# 08-NANDStatusLed.net
KiCad netlist of a schematic drawn in Altium Designer
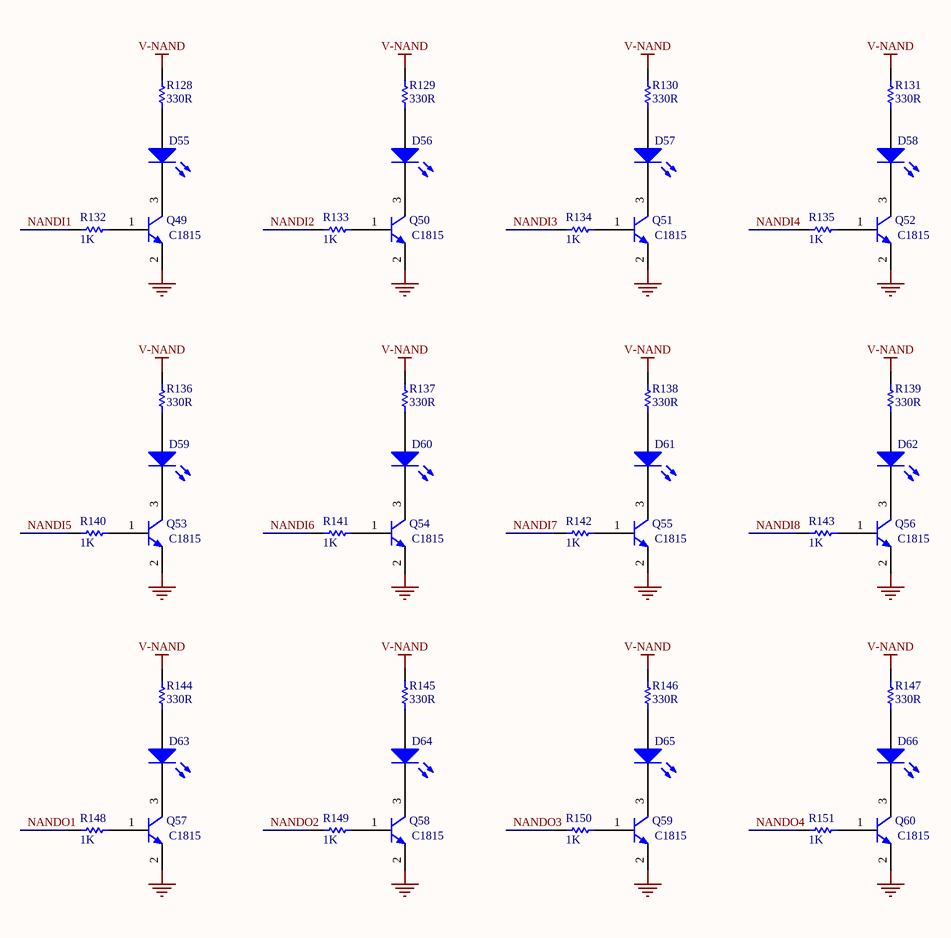
[diagram p0: 08-NANDStatusLed.SchDoc]

(export (version "E")
  (design (tool "Eeschema 10.0.6"))
  (components
    (comp (ref "D55")
      (value "LED")
      (footprint "LED-3528")
      (description "Typical RED, GREEN, YELLOW, AMBER GaAs LED")
      (fields (field (name "PUBLISHER") "Altium Limited"))
      (libsource (lib "Miscellaneous Devices") (part "LED2"))
    )
    (comp (ref "D56")
      (value "LED")
      (footprint "LED-3528")
      (description "Typical RED, GREEN, YELLOW, AMBER GaAs LED")
      (fields (field (name "PUBLISHER") "Altium Limited"))
      (libsource (lib "Miscellaneous Devices") (part "LED2"))
    )
    (comp (ref "D57")
      (value "LED")
      (footprint "LED-3528")
      (description "Typical RED, GREEN, YELLOW, AMBER GaAs LED")
      (fields (field (name "PUBLISHER") "Altium Limited"))
      (libsource (lib "Miscellaneous Devices") (part "LED2"))
    )
    (comp (ref "D58")
      (value "LED")
      (footprint "LED-3528")
      (description "Typical RED, GREEN, YELLOW, AMBER GaAs LED")
      (fields (field (name "PUBLISHER") "Altium Limited"))
      (libsource (lib "Miscellaneous Devices") (part "LED2"))
    )
    (comp (ref "D59")
      (value "LED")
      (footprint "LED-3528")
      (description "Typical RED, GREEN, YELLOW, AMBER GaAs LED")
      (fields (field (name "PUBLISHER") "Altium Limited"))
      (libsource (lib "Miscellaneous Devices") (part "LED2"))
    )
    (comp (ref "D60")
      (value "LED")
      (footprint "LED-3528")
      (description "Typical RED, GREEN, YELLOW, AMBER GaAs LED")
      (fields (field (name "PUBLISHER") "Altium Limited"))
      (libsource (lib "Miscellaneous Devices") (part "LED2"))
    )
    (comp (ref "D61")
      (value "LED")
      (footprint "LED-3528")
      (description "Typical RED, GREEN, YELLOW, AMBER GaAs LED")
      (fields (field (name "PUBLISHER") "Altium Limited"))
      (libsource (lib "Miscellaneous Devices") (part "LED2"))
    )
    (comp (ref "D62")
      (value "LED")
      (footprint "LED-3528")
      (description "Typical RED, GREEN, YELLOW, AMBER GaAs LED")
      (fields (field (name "PUBLISHER") "Altium Limited"))
      (libsource (lib "Miscellaneous Devices") (part "LED2"))
    )
    (comp (ref "D63")
      (value "LED")
      (footprint "LED-3528")
      (description "Typical RED, GREEN, YELLOW, AMBER GaAs LED")
      (fields (field (name "PUBLISHER") "Altium Limited"))
      (libsource (lib "Miscellaneous Devices") (part "LED2"))
    )
    (comp (ref "D64")
      (value "LED")
      (footprint "LED-3528")
      (description "Typical RED, GREEN, YELLOW, AMBER GaAs LED")
      (fields (field (name "PUBLISHER") "Altium Limited"))
      (libsource (lib "Miscellaneous Devices") (part "LED2"))
    )
    (comp (ref "D65")
      (value "LED")
      (footprint "LED-3528")
      (description "Typical RED, GREEN, YELLOW, AMBER GaAs LED")
      (fields (field (name "PUBLISHER") "Altium Limited"))
      (libsource (lib "Miscellaneous Devices") (part "LED2"))
    )
    (comp (ref "D66")
      (value "LED")
      (footprint "LED-3528")
      (description "Typical RED, GREEN, YELLOW, AMBER GaAs LED")
      (fields (field (name "PUBLISHER") "Altium Limited"))
      (libsource (lib "Miscellaneous Devices") (part "LED2"))
    )
    (comp (ref "Q49")
      (value "C1815")
      (footprint "SOT23-321")
      (description "NPN Bipolar Transistor")
      (fields (field (name "Comment") "C1815-SMD"))
      (libsource (lib "Miscellaneous Devices") (part "NPN"))
    )
    (comp (ref "Q50")
      (value "C1815")
      (footprint "SOT23-321")
      (description "NPN Bipolar Transistor")
      (fields (field (name "Comment") "C1815-SMD"))
      (libsource (lib "Miscellaneous Devices") (part "NPN"))
    )
    (comp (ref "Q51")
      (value "C1815")
      (footprint "SOT23-321")
      (description "NPN Bipolar Transistor")
      (fields (field (name "Comment") "C1815-SMD"))
      (libsource (lib "Miscellaneous Devices") (part "NPN"))
    )
    (comp (ref "Q52")
      (value "C1815")
      (footprint "SOT23-321")
      (description "NPN Bipolar Transistor")
      (fields (field (name "Comment") "C1815-SMD"))
      (libsource (lib "Miscellaneous Devices") (part "NPN"))
    )
    (comp (ref "Q53")
      (value "C1815")
      (footprint "SOT23-321")
      (description "NPN Bipolar Transistor")
      (fields (field (name "Comment") "C1815-SMD"))
      (libsource (lib "Miscellaneous Devices") (part "NPN"))
    )
    (comp (ref "Q54")
      (value "C1815")
      (footprint "SOT23-321")
      (description "NPN Bipolar Transistor")
      (fields (field (name "Comment") "C1815-SMD"))
      (libsource (lib "Miscellaneous Devices") (part "NPN"))
    )
    (comp (ref "Q55")
      (value "C1815")
      (footprint "SOT23-321")
      (description "NPN Bipolar Transistor")
      (fields (field (name "Comment") "C1815-SMD"))
      (libsource (lib "Miscellaneous Devices") (part "NPN"))
    )
    (comp (ref "Q56")
      (value "C1815")
      (footprint "SOT23-321")
      (description "NPN Bipolar Transistor")
      (fields (field (name "Comment") "C1815-SMD"))
      (libsource (lib "Miscellaneous Devices") (part "NPN"))
    )
    (comp (ref "Q57")
      (value "C1815")
      (footprint "SOT23-321")
      (description "NPN Bipolar Transistor")
      (fields (field (name "Comment") "C1815-SMD"))
      (libsource (lib "Miscellaneous Devices") (part "NPN"))
    )
    (comp (ref "Q58")
      (value "C1815")
      (footprint "SOT23-321")
      (description "NPN Bipolar Transistor")
      (fields (field (name "Comment") "C1815-SMD"))
      (libsource (lib "Miscellaneous Devices") (part "NPN"))
    )
    (comp (ref "Q59")
      (value "C1815")
      (footprint "SOT23-321")
      (description "NPN Bipolar Transistor")
      (fields (field (name "Comment") "C1815-SMD"))
      (libsource (lib "Miscellaneous Devices") (part "NPN"))
    )
    (comp (ref "Q60")
      (value "C1815")
      (footprint "SOT23-321")
      (description "NPN Bipolar Transistor")
      (fields (field (name "Comment") "C1815-SMD"))
      (libsource (lib "Miscellaneous Devices") (part "NPN"))
    )
    (comp (ref "R128")
      (value "330R")
      (footprint "R-0805")
      (description "Resistor")
      (fields (field (name "PUBLISHER") "Altium Limited"))
      (libsource (lib "Miscellaneous Devices") (part "Res1"))
    )
    (comp (ref "R129")
      (value "330R")
      (footprint "R-0805")
      (description "Resistor")
      (fields (field (name "PUBLISHER") "Altium Limited"))
      (libsource (lib "Miscellaneous Devices") (part "Res1"))
    )
    (comp (ref "R130")
      (value "330R")
      (footprint "R-0805")
      (description "Resistor")
      (fields (field (name "PUBLISHER") "Altium Limited"))
      (libsource (lib "Miscellaneous Devices") (part "Res1"))
    )
    (comp (ref "R131")
      (value "330R")
      (footprint "R-0805")
      (description "Resistor")
      (fields (field (name "PUBLISHER") "Altium Limited"))
      (libsource (lib "Miscellaneous Devices") (part "Res1"))
    )
    (comp (ref "R132")
      (value "1K")
      (footprint "R-0805")
      (description "Resistor")
      (fields (field (name "PUBLISHER") "Altium Limited"))
      (libsource (lib "Miscellaneous Devices") (part "Res1"))
    )
    (comp (ref "R133")
      (value "1K")
      (footprint "R-0805")
      (description "Resistor")
      (fields (field (name "PUBLISHER") "Altium Limited"))
      (libsource (lib "Miscellaneous Devices") (part "Res1"))
    )
    (comp (ref "R134")
      (value "1K")
      (footprint "R-0805")
      (description "Resistor")
      (fields (field (name "PUBLISHER") "Altium Limited"))
      (libsource (lib "Miscellaneous Devices") (part "Res1"))
    )
    (comp (ref "R135")
      (value "1K")
      (footprint "R-0805")
      (description "Resistor")
      (fields (field (name "PUBLISHER") "Altium Limited"))
      (libsource (lib "Miscellaneous Devices") (part "Res1"))
    )
    (comp (ref "R136")
      (value "330R")
      (footprint "R-0805")
      (description "Resistor")
      (fields (field (name "PUBLISHER") "Altium Limited"))
      (libsource (lib "Miscellaneous Devices") (part "Res1"))
    )
    (comp (ref "R137")
      (value "330R")
      (footprint "R-0805")
      (description "Resistor")
      (fields (field (name "PUBLISHER") "Altium Limited"))
      (libsource (lib "Miscellaneous Devices") (part "Res1"))
    )
    (comp (ref "R138")
      (value "330R")
      (footprint "R-0805")
      (description "Resistor")
      (fields (field (name "PUBLISHER") "Altium Limited"))
      (libsource (lib "Miscellaneous Devices") (part "Res1"))
    )
    (comp (ref "R139")
      (value "330R")
      (footprint "R-0805")
      (description "Resistor")
      (fields (field (name "PUBLISHER") "Altium Limited"))
      (libsource (lib "Miscellaneous Devices") (part "Res1"))
    )
    (comp (ref "R140")
      (value "1K")
      (footprint "R-0805")
      (description "Resistor")
      (fields (field (name "PUBLISHER") "Altium Limited"))
      (libsource (lib "Miscellaneous Devices") (part "Res1"))
    )
    (comp (ref "R141")
      (value "1K")
      (footprint "R-0805")
      (description "Resistor")
      (fields (field (name "PUBLISHER") "Altium Limited"))
      (libsource (lib "Miscellaneous Devices") (part "Res1"))
    )
    (comp (ref "R142")
      (value "1K")
      (footprint "R-0805")
      (description "Resistor")
      (fields (field (name "PUBLISHER") "Altium Limited"))
      (libsource (lib "Miscellaneous Devices") (part "Res1"))
    )
    (comp (ref "R143")
      (value "1K")
      (footprint "R-0805")
      (description "Resistor")
      (fields (field (name "PUBLISHER") "Altium Limited"))
      (libsource (lib "Miscellaneous Devices") (part "Res1"))
    )
    (comp (ref "R144")
      (value "330R")
      (footprint "R-0805")
      (description "Resistor")
      (fields (field (name "PUBLISHER") "Altium Limited"))
      (libsource (lib "Miscellaneous Devices") (part "Res1"))
    )
    (comp (ref "R145")
      (value "330R")
      (footprint "R-0805")
      (description "Resistor")
      (fields (field (name "PUBLISHER") "Altium Limited"))
      (libsource (lib "Miscellaneous Devices") (part "Res1"))
    )
    (comp (ref "R146")
      (value "330R")
      (footprint "R-0805")
      (description "Resistor")
      (fields (field (name "PUBLISHER") "Altium Limited"))
      (libsource (lib "Miscellaneous Devices") (part "Res1"))
    )
    (comp (ref "R147")
      (value "330R")
      (footprint "R-0805")
      (description "Resistor")
      (fields (field (name "PUBLISHER") "Altium Limited"))
      (libsource (lib "Miscellaneous Devices") (part "Res1"))
    )
    (comp (ref "R148")
      (value "1K")
      (footprint "R-0805")
      (description "Resistor")
      (fields (field (name "PUBLISHER") "Altium Limited"))
      (libsource (lib "Miscellaneous Devices") (part "Res1"))
    )
    (comp (ref "R149")
      (value "1K")
      (footprint "R-0805")
      (description "Resistor")
      (fields (field (name "PUBLISHER") "Altium Limited"))
      (libsource (lib "Miscellaneous Devices") (part "Res1"))
    )
    (comp (ref "R150")
      (value "1K")
      (footprint "R-0805")
      (description "Resistor")
      (fields (field (name "PUBLISHER") "Altium Limited"))
      (libsource (lib "Miscellaneous Devices") (part "Res1"))
    )
    (comp (ref "R151")
      (value "1K")
      (footprint "R-0805")
      (description "Resistor")
      (fields (field (name "PUBLISHER") "Altium Limited"))
      (libsource (lib "Miscellaneous Devices") (part "Res1"))
    )
  )
  (nets
    (net (code "1") (name "/NANDI1") (class "Default")
      (node (ref "R132") (pin "2") (pinfunction "2_2") (pintype "passive"))
    )
    (net (code "2") (name "/NANDI2") (class "Default")
      (node (ref "R133") (pin "2") (pinfunction "2_2") (pintype "passive"))
    )
    (net (code "3") (name "/NANDI3") (class "Default")
      (node (ref "R134") (pin "2") (pinfunction "2_2") (pintype "passive"))
    )
    (net (code "4") (name "/NANDI4") (class "Default")
      (node (ref "R135") (pin "2") (pinfunction "2_2") (pintype "passive"))
    )
    (net (code "5") (name "/NANDI5") (class "Default")
      (node (ref "R140") (pin "2") (pinfunction "2_2") (pintype "passive"))
    )
    (net (code "6") (name "/NANDI6") (class "Default")
      (node (ref "R141") (pin "2") (pinfunction "2_2") (pintype "passive"))
    )
    (net (code "7") (name "/NANDI7") (class "Default")
      (node (ref "R142") (pin "2") (pinfunction "2_2") (pintype "passive"))
    )
    (net (code "8") (name "/NANDI8") (class "Default")
      (node (ref "R143") (pin "2") (pinfunction "2_2") (pintype "passive"))
    )
    (net (code "9") (name "/NANDO1") (class "Default")
      (node (ref "R148") (pin "2") (pinfunction "2_2") (pintype "passive"))
    )
    (net (code "10") (name "/NANDO2") (class "Default")
      (node (ref "R149") (pin "2") (pinfunction "2_2") (pintype "passive"))
    )
    (net (code "11") (name "/NANDO3") (class "Default")
      (node (ref "R150") (pin "2") (pinfunction "2_2") (pintype "passive"))
    )
    (net (code "12") (name "/NANDO4") (class "Default")
      (node (ref "R151") (pin "2") (pinfunction "2_2") (pintype "passive"))
    )
    (net (code "13") (name "GND") (class "Default")
      (node (ref "Q49") (pin "2") (pinfunction "E_2") (pintype "passive"))
      (node (ref "Q50") (pin "2") (pinfunction "E_2") (pintype "passive"))
      (node (ref "Q51") (pin "2") (pinfunction "E_2") (pintype "passive"))
      (node (ref "Q52") (pin "2") (pinfunction "E_2") (pintype "passive"))
      (node (ref "Q53") (pin "2") (pinfunction "E_2") (pintype "passive"))
      (node (ref "Q54") (pin "2") (pinfunction "E_2") (pintype "passive"))
      (node (ref "Q55") (pin "2") (pinfunction "E_2") (pintype "passive"))
      (node (ref "Q56") (pin "2") (pinfunction "E_2") (pintype "passive"))
      (node (ref "Q57") (pin "2") (pinfunction "E_2") (pintype "passive"))
      (node (ref "Q58") (pin "2") (pinfunction "E_2") (pintype "passive"))
      (node (ref "Q59") (pin "2") (pinfunction "E_2") (pintype "passive"))
      (node (ref "Q60") (pin "2") (pinfunction "E_2") (pintype "passive"))
    )
    (net (code "14") (name "Net-(D55-A)") (class "Default")
      (node (ref "D55") (pin "1") (pinfunction "A_1") (pintype "passive"))
      (node (ref "R128") (pin "1") (pinfunction "1_1") (pintype "passive"))
    )
    (net (code "15") (name "Net-(D55-K)") (class "Default")
      (node (ref "D55") (pin "2") (pinfunction "K_2") (pintype "passive"))
      (node (ref "Q49") (pin "3") (pinfunction "C_3") (pintype "passive"))
    )
    (net (code "16") (name "Net-(D56-A)") (class "Default")
      (node (ref "D56") (pin "1") (pinfunction "A_1") (pintype "passive"))
      (node (ref "R129") (pin "1") (pinfunction "1_1") (pintype "passive"))
    )
    (net (code "17") (name "Net-(D56-K)") (class "Default")
      (node (ref "D56") (pin "2") (pinfunction "K_2") (pintype "passive"))
      (node (ref "Q50") (pin "3") (pinfunction "C_3") (pintype "passive"))
    )
    (net (code "18") (name "Net-(D57-A)") (class "Default")
      (node (ref "D57") (pin "1") (pinfunction "A_1") (pintype "passive"))
      (node (ref "R130") (pin "1") (pinfunction "1_1") (pintype "passive"))
    )
    (net (code "19") (name "Net-(D57-K)") (class "Default")
      (node (ref "D57") (pin "2") (pinfunction "K_2") (pintype "passive"))
      (node (ref "Q51") (pin "3") (pinfunction "C_3") (pintype "passive"))
    )
    (net (code "20") (name "Net-(D58-A)") (class "Default")
      (node (ref "D58") (pin "1") (pinfunction "A_1") (pintype "passive"))
      (node (ref "R131") (pin "1") (pinfunction "1_1") (pintype "passive"))
    )
    (net (code "21") (name "Net-(D58-K)") (class "Default")
      (node (ref "D58") (pin "2") (pinfunction "K_2") (pintype "passive"))
      (node (ref "Q52") (pin "3") (pinfunction "C_3") (pintype "passive"))
    )
    (net (code "22") (name "Net-(D59-A)") (class "Default")
      (node (ref "D59") (pin "1") (pinfunction "A_1") (pintype "passive"))
      (node (ref "R136") (pin "1") (pinfunction "1_1") (pintype "passive"))
    )
    (net (code "23") (name "Net-(D59-K)") (class "Default")
      (node (ref "D59") (pin "2") (pinfunction "K_2") (pintype "passive"))
      (node (ref "Q53") (pin "3") (pinfunction "C_3") (pintype "passive"))
    )
    (net (code "24") (name "Net-(D60-A)") (class "Default")
      (node (ref "D60") (pin "1") (pinfunction "A_1") (pintype "passive"))
      (node (ref "R137") (pin "1") (pinfunction "1_1") (pintype "passive"))
    )
    (net (code "25") (name "Net-(D60-K)") (class "Default")
      (node (ref "D60") (pin "2") (pinfunction "K_2") (pintype "passive"))
      (node (ref "Q54") (pin "3") (pinfunction "C_3") (pintype "passive"))
    )
    (net (code "26") (name "Net-(D61-A)") (class "Default")
      (node (ref "D61") (pin "1") (pinfunction "A_1") (pintype "passive"))
      (node (ref "R138") (pin "1") (pinfunction "1_1") (pintype "passive"))
    )
    (net (code "27") (name "Net-(D61-K)") (class "Default")
      (node (ref "D61") (pin "2") (pinfunction "K_2") (pintype "passive"))
      (node (ref "Q55") (pin "3") (pinfunction "C_3") (pintype "passive"))
    )
    (net (code "28") (name "Net-(D62-A)") (class "Default")
      (node (ref "D62") (pin "1") (pinfunction "A_1") (pintype "passive"))
      (node (ref "R139") (pin "1") (pinfunction "1_1") (pintype "passive"))
    )
    (net (code "29") (name "Net-(D62-K)") (class "Default")
      (node (ref "D62") (pin "2") (pinfunction "K_2") (pintype "passive"))
      (node (ref "Q56") (pin "3") (pinfunction "C_3") (pintype "passive"))
    )
    (net (code "30") (name "Net-(D63-A)") (class "Default")
      (node (ref "D63") (pin "1") (pinfunction "A_1") (pintype "passive"))
      (node (ref "R144") (pin "1") (pinfunction "1_1") (pintype "passive"))
    )
    (net (code "31") (name "Net-(D63-K)") (class "Default")
      (node (ref "D63") (pin "2") (pinfunction "K_2") (pintype "passive"))
      (node (ref "Q57") (pin "3") (pinfunction "C_3") (pintype "passive"))
    )
    (net (code "32") (name "Net-(D64-A)") (class "Default")
      (node (ref "D64") (pin "1") (pinfunction "A_1") (pintype "passive"))
      (node (ref "R145") (pin "1") (pinfunction "1_1") (pintype "passive"))
    )
    (net (code "33") (name "Net-(D64-K)") (class "Default")
      (node (ref "D64") (pin "2") (pinfunction "K_2") (pintype "passive"))
      (node (ref "Q58") (pin "3") (pinfunction "C_3") (pintype "passive"))
    )
    (net (code "34") (name "Net-(D65-A)") (class "Default")
      (node (ref "D65") (pin "1") (pinfunction "A_1") (pintype "passive"))
      (node (ref "R146") (pin "1") (pinfunction "1_1") (pintype "passive"))
    )
    (net (code "35") (name "Net-(D65-K)") (class "Default")
      (node (ref "D65") (pin "2") (pinfunction "K_2") (pintype "passive"))
      (node (ref "Q59") (pin "3") (pinfunction "C_3") (pintype "passive"))
    )
    (net (code "36") (name "Net-(D66-A)") (class "Default")
      (node (ref "D66") (pin "1") (pinfunction "A_1") (pintype "passive"))
      (node (ref "R147") (pin "1") (pinfunction "1_1") (pintype "passive"))
    )
    (net (code "37") (name "Net-(D66-K)") (class "Default")
      (node (ref "D66") (pin "2") (pinfunction "K_2") (pintype "passive"))
      (node (ref "Q60") (pin "3") (pinfunction "C_3") (pintype "passive"))
    )
    (net (code "38") (name "Net-(Q49-B)") (class "Default")
      (node (ref "Q49") (pin "1") (pinfunction "B_1") (pintype "passive"))
      (node (ref "R132") (pin "1") (pinfunction "1_1") (pintype "passive"))
    )
    (net (code "39") (name "Net-(Q50-B)") (class "Default")
      (node (ref "Q50") (pin "1") (pinfunction "B_1") (pintype "passive"))
      (node (ref "R133") (pin "1") (pinfunction "1_1") (pintype "passive"))
    )
    (net (code "40") (name "Net-(Q51-B)") (class "Default")
      (node (ref "Q51") (pin "1") (pinfunction "B_1") (pintype "passive"))
      (node (ref "R134") (pin "1") (pinfunction "1_1") (pintype "passive"))
    )
    (net (code "41") (name "Net-(Q52-B)") (class "Default")
      (node (ref "Q52") (pin "1") (pinfunction "B_1") (pintype "passive"))
      (node (ref "R135") (pin "1") (pinfunction "1_1") (pintype "passive"))
    )
    (net (code "42") (name "Net-(Q53-B)") (class "Default")
      (node (ref "Q53") (pin "1") (pinfunction "B_1") (pintype "passive"))
      (node (ref "R140") (pin "1") (pinfunction "1_1") (pintype "passive"))
    )
    (net (code "43") (name "Net-(Q54-B)") (class "Default")
      (node (ref "Q54") (pin "1") (pinfunction "B_1") (pintype "passive"))
      (node (ref "R141") (pin "1") (pinfunction "1_1") (pintype "passive"))
    )
    (net (code "44") (name "Net-(Q55-B)") (class "Default")
      (node (ref "Q55") (pin "1") (pinfunction "B_1") (pintype "passive"))
      (node (ref "R142") (pin "1") (pinfunction "1_1") (pintype "passive"))
    )
    (net (code "45") (name "Net-(Q56-B)") (class "Default")
      (node (ref "Q56") (pin "1") (pinfunction "B_1") (pintype "passive"))
      (node (ref "R143") (pin "1") (pinfunction "1_1") (pintype "passive"))
    )
    (net (code "46") (name "Net-(Q57-B)") (class "Default")
      (node (ref "Q57") (pin "1") (pinfunction "B_1") (pintype "passive"))
      (node (ref "R148") (pin "1") (pinfunction "1_1") (pintype "passive"))
    )
    (net (code "47") (name "Net-(Q58-B)") (class "Default")
      (node (ref "Q58") (pin "1") (pinfunction "B_1") (pintype "passive"))
      (node (ref "R149") (pin "1") (pinfunction "1_1") (pintype "passive"))
    )
    (net (code "48") (name "Net-(Q59-B)") (class "Default")
      (node (ref "Q59") (pin "1") (pinfunction "B_1") (pintype "passive"))
      (node (ref "R150") (pin "1") (pinfunction "1_1") (pintype "passive"))
    )
    (net (code "49") (name "Net-(Q60-B)") (class "Default")
      (node (ref "Q60") (pin "1") (pinfunction "B_1") (pintype "passive"))
      (node (ref "R151") (pin "1") (pinfunction "1_1") (pintype "passive"))
    )
    (net (code "50") (name "V-NAND") (class "Default")
      (node (ref "R128") (pin "2") (pinfunction "2_2") (pintype "passive"))
      (node (ref "R129") (pin "2") (pinfunction "2_2") (pintype "passive"))
      (node (ref "R130") (pin "2") (pinfunction "2_2") (pintype "passive"))
      (node (ref "R131") (pin "2") (pinfunction "2_2") (pintype "passive"))
      (node (ref "R136") (pin "2") (pinfunction "2_2") (pintype "passive"))
      (node (ref "R137") (pin "2") (pinfunction "2_2") (pintype "passive"))
      (node (ref "R138") (pin "2") (pinfunction "2_2") (pintype "passive"))
      (node (ref "R139") (pin "2") (pinfunction "2_2") (pintype "passive"))
      (node (ref "R144") (pin "2") (pinfunction "2_2") (pintype "passive"))
      (node (ref "R145") (pin "2") (pinfunction "2_2") (pintype "passive"))
      (node (ref "R146") (pin "2") (pinfunction "2_2") (pintype "passive"))
      (node (ref "R147") (pin "2") (pinfunction "2_2") (pintype "passive"))
    )
  )
)
